# ProPrj___2024-08-31.net
KiCad netlist of a schematic drawn in EasyEDA Pro
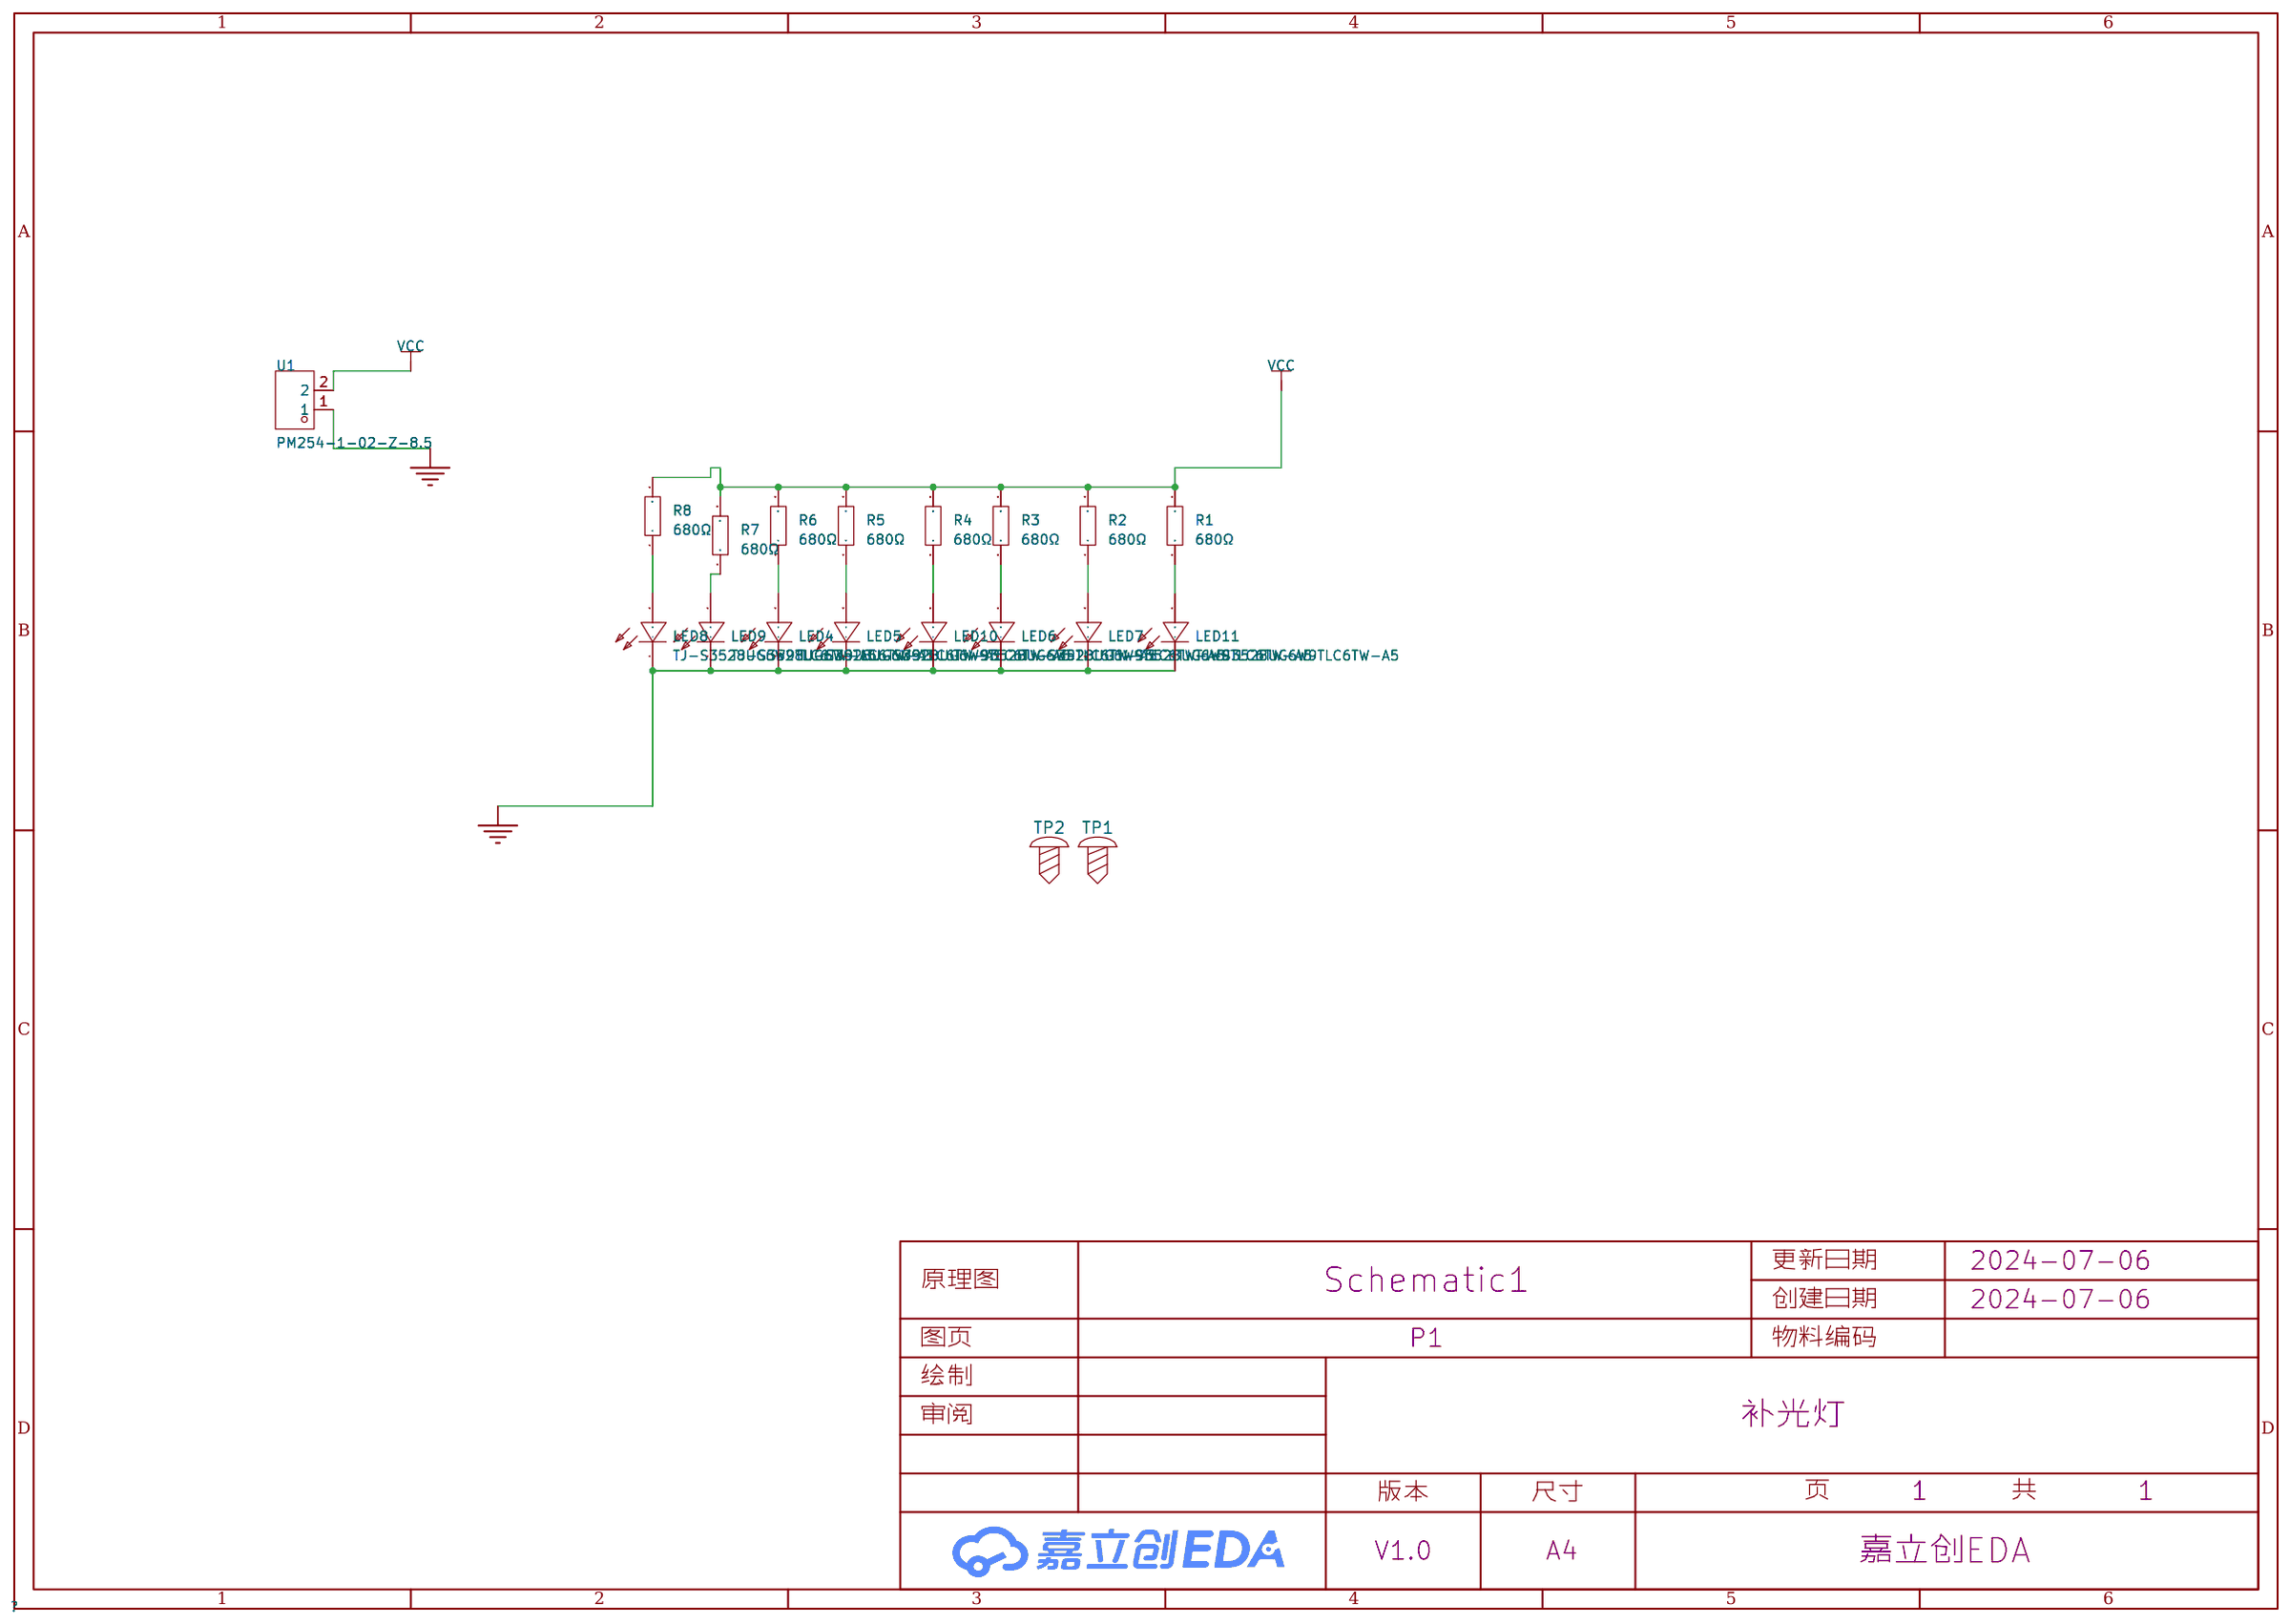
[diagram p0: schematic sheet]

(export (version "E")
  (design (tool "Eeschema 10.0.6"))
  (components
    (comp (ref "LED4")
      (value "TJ-S3528UG6W9TLC6TW-A5")
      (footprint "easyedapro:LED-SMD_L3.2-W2.8-R-RD")
      (description "发光颜色:白色;功率:108mW;正向电流:20mA;主波长:-;二极管配置:-;透镜颜色:-;色温:5500K~7000K;发光角度:120°;载带方式:-;工作温度:-40°C~+80°C;")
      (fields (field (name "Manufacturer") "TOGIALED(统佳)"))
      (libsource (lib "easyedapro") (part "TJ-S3528UG6W9TLC6TW-A5"))
    )
    (comp (ref "LED5")
      (value "TJ-S3528UG6W9TLC6TW-A5")
      (footprint "easyedapro:LED-SMD_L3.2-W2.8-R-RD")
      (description "发光颜色:白色;功率:108mW;正向电流:20mA;主波长:-;二极管配置:-;透镜颜色:-;色温:5500K~7000K;发光角度:120°;载带方式:-;工作温度:-40°C~+80°C;")
      (fields (field (name "Manufacturer") "TOGIALED(统佳)"))
      (libsource (lib "easyedapro") (part "TJ-S3528UG6W9TLC6TW-A5"))
    )
    (comp (ref "LED6")
      (value "TJ-S3528UG6W9TLC6TW-A5")
      (footprint "easyedapro:LED-SMD_L3.2-W2.8-R-RD")
      (description "发光颜色:白色;功率:108mW;正向电流:20mA;主波长:-;二极管配置:-;透镜颜色:-;色温:5500K~7000K;发光角度:120°;载带方式:-;工作温度:-40°C~+80°C;")
      (fields (field (name "Manufacturer") "TOGIALED(统佳)"))
      (libsource (lib "easyedapro") (part "TJ-S3528UG6W9TLC6TW-A5"))
    )
    (comp (ref "LED7")
      (value "TJ-S3528UG6W9TLC6TW-A5")
      (footprint "easyedapro:LED-SMD_L3.2-W2.8-R-RD")
      (description "发光颜色:白色;功率:108mW;正向电流:20mA;主波长:-;二极管配置:-;透镜颜色:-;色温:5500K~7000K;发光角度:120°;载带方式:-;工作温度:-40°C~+80°C;")
      (fields (field (name "Manufacturer") "TOGIALED(统佳)"))
      (libsource (lib "easyedapro") (part "TJ-S3528UG6W9TLC6TW-A5"))
    )
    (comp (ref "LED8")
      (value "TJ-S3528UG6W9TLC6TW-A5")
      (footprint "easyedapro:LED-SMD_L3.2-W2.8-R-RD")
      (description "发光颜色:白色;功率:108mW;正向电流:20mA;主波长:-;二极管配置:-;透镜颜色:-;色温:5500K~7000K;发光角度:120°;载带方式:-;工作温度:-40°C~+80°C;")
      (fields (field (name "Manufacturer") "TOGIALED(统佳)"))
      (libsource (lib "easyedapro") (part "TJ-S3528UG6W9TLC6TW-A5"))
    )
    (comp (ref "LED9")
      (value "TJ-S3528UG6W9TLC6TW-A5")
      (footprint "easyedapro:LED-SMD_L3.2-W2.8-R-RD")
      (description "发光颜色:白色;功率:108mW;正向电流:20mA;主波长:-;二极管配置:-;透镜颜色:-;色温:5500K~7000K;发光角度:120°;载带方式:-;工作温度:-40°C~+80°C;")
      (fields (field (name "Manufacturer") "TOGIALED(统佳)"))
      (libsource (lib "easyedapro") (part "TJ-S3528UG6W9TLC6TW-A5"))
    )
    (comp (ref "LED10")
      (value "TJ-S3528UG6W9TLC6TW-A5")
      (footprint "easyedapro:LED-SMD_L3.2-W2.8-R-RD")
      (description "发光颜色:白色;功率:108mW;正向电流:20mA;主波长:-;二极管配置:-;透镜颜色:-;色温:5500K~7000K;发光角度:120°;载带方式:-;工作温度:-40°C~+80°C;")
      (fields (field (name "Manufacturer") "TOGIALED(统佳)"))
      (libsource (lib "easyedapro") (part "TJ-S3528UG6W9TLC6TW-A5"))
    )
    (comp (ref "LED11")
      (value "TJ-S3528UG6W9TLC6TW-A5")
      (footprint "easyedapro:LED-SMD_L3.2-W2.8-R-RD")
      (description "发光颜色:白色;功率:108mW;正向电流:20mA;主波长:-;二极管配置:-;透镜颜色:-;色温:5500K~7000K;发光角度:120°;载带方式:-;工作温度:-40°C~+80°C;")
      (fields (field (name "Manufacturer") "TOGIALED(统佳)"))
      (libsource (lib "easyedapro") (part "TJ-S3528UG6W9TLC6TW-A5"))
    )
    (comp (ref "R1")
      (value "680Ω")
      (footprint "easyedapro:R0805")
      (description "电阻类型:厚膜电阻;阻值:680Ω;精度:±1%;功率:125mW;最大工作电压:150V;温度系数:±100ppm/°C;")
      (fields
        (field (name "Manufacturer Part") "0805W8F6800T5E")
        (field (name "Manufacturer") "UNI-ROYAL(厚声)")
      )
      (libsource (lib "easyedapro") (part "0805W8F6800T5E"))
    )
    (comp (ref "R2")
      (value "680Ω")
      (footprint "easyedapro:R0805")
      (description "电阻类型:厚膜电阻;阻值:680Ω;精度:±1%;功率:125mW;最大工作电压:150V;温度系数:±100ppm/°C;")
      (fields
        (field (name "Manufacturer Part") "0805W8F6800T5E")
        (field (name "Manufacturer") "UNI-ROYAL(厚声)")
      )
      (libsource (lib "easyedapro") (part "0805W8F6800T5E"))
    )
    (comp (ref "R3")
      (value "680Ω")
      (footprint "easyedapro:R0805")
      (description "电阻类型:厚膜电阻;阻值:680Ω;精度:±1%;功率:125mW;最大工作电压:150V;温度系数:±100ppm/°C;")
      (fields
        (field (name "Manufacturer Part") "0805W8F6800T5E")
        (field (name "Manufacturer") "UNI-ROYAL(厚声)")
      )
      (libsource (lib "easyedapro") (part "0805W8F6800T5E"))
    )
    (comp (ref "R4")
      (value "680Ω")
      (footprint "easyedapro:R0805")
      (description "电阻类型:厚膜电阻;阻值:680Ω;精度:±1%;功率:125mW;最大工作电压:150V;温度系数:±100ppm/°C;")
      (fields
        (field (name "Manufacturer Part") "0805W8F6800T5E")
        (field (name "Manufacturer") "UNI-ROYAL(厚声)")
      )
      (libsource (lib "easyedapro") (part "0805W8F6800T5E"))
    )
    (comp (ref "R5")
      (value "680Ω")
      (footprint "easyedapro:R0805")
      (description "电阻类型:厚膜电阻;阻值:680Ω;精度:±1%;功率:125mW;最大工作电压:150V;温度系数:±100ppm/°C;")
      (fields
        (field (name "Manufacturer Part") "0805W8F6800T5E")
        (field (name "Manufacturer") "UNI-ROYAL(厚声)")
      )
      (libsource (lib "easyedapro") (part "0805W8F6800T5E"))
    )
    (comp (ref "R6")
      (value "680Ω")
      (footprint "easyedapro:R0805")
      (description "电阻类型:厚膜电阻;阻值:680Ω;精度:±1%;功率:125mW;最大工作电压:150V;温度系数:±100ppm/°C;")
      (fields
        (field (name "Manufacturer Part") "0805W8F6800T5E")
        (field (name "Manufacturer") "UNI-ROYAL(厚声)")
      )
      (libsource (lib "easyedapro") (part "0805W8F6800T5E"))
    )
    (comp (ref "R7")
      (value "680Ω")
      (footprint "easyedapro:R0805")
      (description "电阻类型:厚膜电阻;阻值:680Ω;精度:±1%;功率:125mW;最大工作电压:150V;温度系数:±100ppm/°C;")
      (fields
        (field (name "Manufacturer Part") "0805W8F6800T5E")
        (field (name "Manufacturer") "UNI-ROYAL(厚声)")
      )
      (libsource (lib "easyedapro") (part "0805W8F6800T5E"))
    )
    (comp (ref "R8")
      (value "680Ω")
      (footprint "easyedapro:R0805")
      (description "电阻类型:厚膜电阻;阻值:680Ω;精度:±1%;功率:125mW;最大工作电压:150V;温度系数:±100ppm/°C;")
      (fields
        (field (name "Manufacturer Part") "0805W8F6800T5E")
        (field (name "Manufacturer") "UNI-ROYAL(厚声)")
      )
      (libsource (lib "easyedapro") (part "0805W8F6800T5E"))
    )
    (comp (ref "TP1")
      (value "M3铜柱带丝印")
      (footprint "easyedapro:M3铜柱")
      (libsource (lib "easyedapro") (part "M3铜柱带丝印"))
    )
    (comp (ref "TP2")
      (value "M3铜柱带丝印")
      (footprint "easyedapro:M3铜柱")
      (libsource (lib "easyedapro") (part "M3铜柱带丝印"))
    )
    (comp (ref "U1")
      (value "PM254-1-02-Z-8.5")
      (footprint "easyedapro:HDR-TH_2P-P2.54-V-F")
      (fields (field (name "Manufacturer") "HCTL(华灿天禄)"))
      (libsource (lib "easyedapro") (part "PM254-1-02-Z-8.5"))
    )
  )
  (nets
    (net (code "1") (name "GND") (class "Default")
      (node (ref "LED10") (pin "1") (pinfunction "-_1") (pintype "unspecified"))
      (node (ref "LED11") (pin "1") (pinfunction "-_1") (pintype "unspecified"))
      (node (ref "LED4") (pin "1") (pinfunction "-_1") (pintype "unspecified"))
      (node (ref "LED5") (pin "1") (pinfunction "-_1") (pintype "unspecified"))
      (node (ref "LED6") (pin "1") (pinfunction "-_1") (pintype "unspecified"))
      (node (ref "LED7") (pin "1") (pinfunction "-_1") (pintype "unspecified"))
      (node (ref "LED8") (pin "1") (pinfunction "-_1") (pintype "unspecified"))
      (node (ref "LED9") (pin "1") (pinfunction "-_1") (pintype "unspecified"))
      (node (ref "U1") (pin "1") (pinfunction "1_1") (pintype "unspecified"))
    )
    (net (code "2") (name "Net-(LED4-+)") (class "Default")
      (node (ref "LED4") (pin "2") (pinfunction "+_2") (pintype "unspecified"))
      (node (ref "R6") (pin "1") (pinfunction "1_1") (pintype "input"))
    )
    (net (code "3") (name "Net-(LED5-+)") (class "Default")
      (node (ref "LED5") (pin "2") (pinfunction "+_2") (pintype "unspecified"))
      (node (ref "R5") (pin "1") (pinfunction "1_1") (pintype "input"))
    )
    (net (code "4") (name "Net-(LED6-+)") (class "Default")
      (node (ref "LED6") (pin "2") (pinfunction "+_2") (pintype "unspecified"))
      (node (ref "R3") (pin "1") (pinfunction "1_1") (pintype "input"))
    )
    (net (code "5") (name "Net-(LED7-+)") (class "Default")
      (node (ref "LED7") (pin "2") (pinfunction "+_2") (pintype "unspecified"))
      (node (ref "R2") (pin "1") (pinfunction "1_1") (pintype "input"))
    )
    (net (code "6") (name "Net-(LED8-+)") (class "Default")
      (node (ref "LED8") (pin "2") (pinfunction "+_2") (pintype "unspecified"))
      (node (ref "R8") (pin "1") (pinfunction "1_1") (pintype "input"))
    )
    (net (code "7") (name "Net-(LED9-+)") (class "Default")
      (node (ref "LED9") (pin "2") (pinfunction "+_2") (pintype "unspecified"))
      (node (ref "R7") (pin "1") (pinfunction "1_1") (pintype "input"))
    )
    (net (code "8") (name "Net-(LED10-+)") (class "Default")
      (node (ref "LED10") (pin "2") (pinfunction "+_2") (pintype "unspecified"))
      (node (ref "R4") (pin "1") (pinfunction "1_1") (pintype "input"))
    )
    (net (code "9") (name "Net-(LED11-+)") (class "Default")
      (node (ref "LED11") (pin "2") (pinfunction "+_2") (pintype "unspecified"))
      (node (ref "R1") (pin "1") (pinfunction "1_1") (pintype "input"))
    )
    (net (code "10") (name "VCC") (class "Default")
      (node (ref "R1") (pin "2") (pinfunction "2_2") (pintype "input"))
      (node (ref "R2") (pin "2") (pinfunction "2_2") (pintype "input"))
      (node (ref "R3") (pin "2") (pinfunction "2_2") (pintype "input"))
      (node (ref "R4") (pin "2") (pinfunction "2_2") (pintype "input"))
      (node (ref "R5") (pin "2") (pinfunction "2_2") (pintype "input"))
      (node (ref "R6") (pin "2") (pinfunction "2_2") (pintype "input"))
      (node (ref "R7") (pin "2") (pinfunction "2_2") (pintype "input"))
      (node (ref "R8") (pin "2") (pinfunction "2_2") (pintype "input"))
      (node (ref "U1") (pin "2") (pinfunction "2_2") (pintype "unspecified"))
    )
  )
)
